# Main.net
KiCad netlist of a schematic drawn in Altium Designer
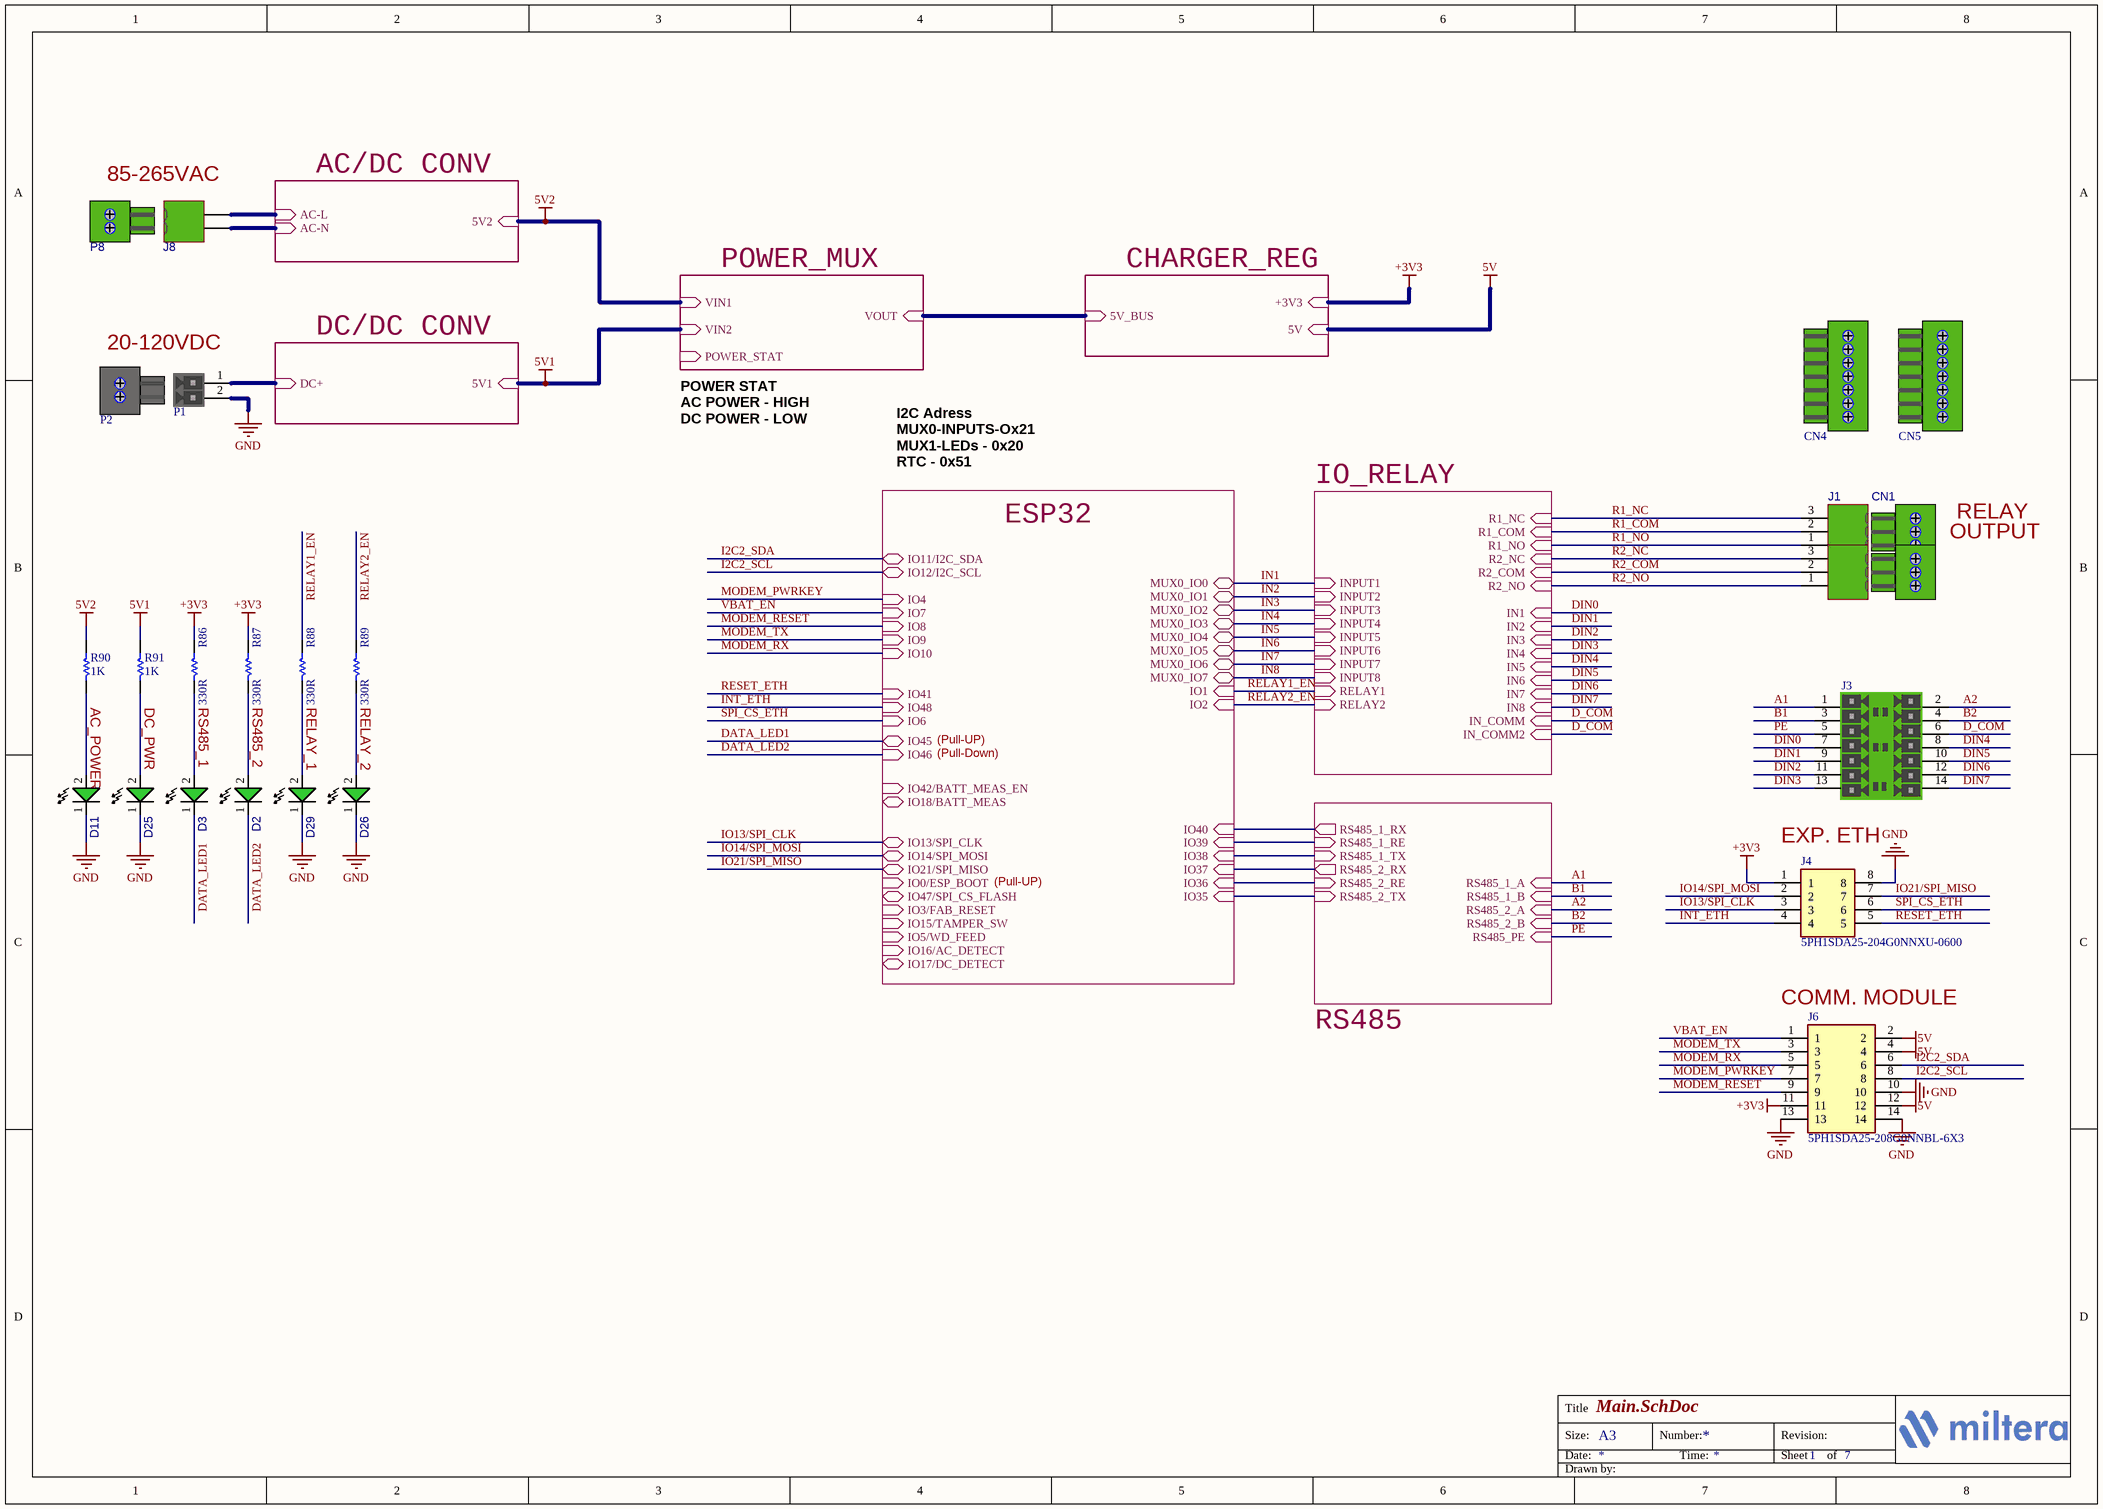
[diagram p0: Main.SchDoc]

(export (version "E")
  (design (tool "Eeschema 10.0.6"))
  (components
    (comp (ref "CN1")
      (value "2EDGK-5.08-06P-14-00AH")
      (footprint "2EDGK-5.08-06P-14-00AH")
      (description "TERM.BLK.5.08MM 6P FEMALE GREEN")
      (fields (field (name "MANUFACTURER") "DEGSON"))
      (libsource (lib "Connectors") (part "2EDGK-5.08-03P-14-00AH"))
    )
    (comp (ref "CN2")
      (value "2EDGRC-5.08-03P-14-00SH")
      (footprint "2EDGRC-5.08-03P-14-00SH")
      (description "TERM.BLK.5.08MM 3P 90C MALE GREEN CLOSED")
      (fields (field (name "MANUFACTURER") "GAOSONG"))
      (libsource (lib "Connectors") (part "2EDGRC-5.08-03P-14-00SH"))
    )
    (comp (ref "CN3")
      (value "2EDGK-5.08-03P-14-00AH")
      (footprint "2EDGK-5.08-06P-14-00AH")
      (description "TERM.BLK.5.08MM 3P FEMALE GREEN")
      (fields (field (name "MANUFACTURER") "DEGSON"))
      (libsource (lib "Connectors") (part "2EDGK-5.08-03P-14-00AH"))
    )
    (comp (ref "CN4")
      (value "15EDGK-3.81-07P-14-00AH")
      (footprint "15EDGK-3.81-07P")
      (description "TERM.BLK.3.81MM 7P FEMALE GREEN")
      (fields (field (name "MANUFACTURER") "DEGSON"))
      (libsource (lib "MTOSOS_R02") (part "15EDGK-3.81-07P-14-00AH"))
    )
    (comp (ref "CN5")
      (value "15EDGK-3.81-07P-14-00AH")
      (footprint "15EDGK-3.81-07P")
      (description "TERM.BLK.3.81MM 7P FEMALE GREEN")
      (fields (field (name "MANUFACTURER") "DEGSON"))
      (libsource (lib "MTOSOS_R02") (part "15EDGK-3.81-07P-14-00AH"))
    )
    (comp (ref "D2")
      (value "PSC-1608U52GC-G4")
      (footprint "LED_0603_GRN")
      (description "LED GREEN WATER CLEAR 0603 SMD")
      (fields (field (name "MANUFACTURER") "HONGLITRONIC"))
      (libsource (lib "Semiconductors") (part "LTST-C190TGKT"))
    )
    (comp (ref "D3")
      (value "PSC-1608U52GC-G4")
      (footprint "LED_0603_GRN")
      (description "LED GREEN WATER CLEAR 0603 SMD")
      (fields (field (name "MANUFACTURER") "HONGLITRONIC"))
      (libsource (lib "Semiconductors") (part "LTST-C190TGKT"))
    )
    (comp (ref "D11")
      (value "PSC-1608U52GC-G4")
      (footprint "LED_0603_GRN")
      (description "LED GREEN WATER CLEAR 0603 SMD")
      (fields (field (name "MANUFACTURER") "HONGLITRONIC"))
      (libsource (lib "Semiconductors") (part "LTST-C190TGKT"))
    )
    (comp (ref "D25")
      (value "PSC-1608U52GC-G4")
      (footprint "LED_0603_GRN")
      (description "LED GREEN WATER CLEAR 0603 SMD")
      (fields (field (name "MANUFACTURER") "HONGLITRONIC"))
      (libsource (lib "Semiconductors") (part "LTST-C190TGKT"))
    )
    (comp (ref "D26")
      (value "PSC-1608U52GC-G4")
      (footprint "LED_0603_GRN")
      (description "LED GREEN WATER CLEAR 0603 SMD")
      (fields (field (name "MANUFACTURER") "HONGLITRONIC"))
      (libsource (lib "Semiconductors") (part "LTST-C190TGKT"))
    )
    (comp (ref "D29")
      (value "PSC-1608U52GC-G4")
      (footprint "LED_0603_GRN")
      (description "LED GREEN WATER CLEAR 0603 SMD")
      (fields (field (name "MANUFACTURER") "HONGLITRONIC"))
      (libsource (lib "Semiconductors") (part "LTST-C190TGKT"))
    )
    (comp (ref "J1")
      (value "2EDGRC-5.08-06P-14-00SH")
      (footprint "2EDGRC-5.08-03P-14-00SH")
      (description "TERM.BLK.5.08MM 6P 90C MALE GREEN CLOSED")
      (fields (field (name "MANUFACTURER") "DEGSON"))
      (libsource (lib "Connectors") (part "2EDGRC-5.08-03P-14-00SH"))
    )
    (comp (ref "J3")
      (value "15EDGRH-3.81-12P-14-00AH")
      (footprint "15EDGRH-3.81-14P")
      (description "TERM.BLK.3.81mm 14P 90C MALE GREEN CLOSED")
      (fields (field (name "MANUFACTURER") "DEGSON"))
      (libsource (lib "MTOSOS_R02") (part "15EDGRH-3.81-12P-14-00AH"))
    )
    (comp (ref "J4")
      (value "5PH1SDA25-204G0NNXU-0600")
      (footprint "SamacSys:61300821121")
      (description "MALE HEADER 8PIN(2X4) 2.54MM THT 6X3MM")
      (fields (field (name "MANUFACTURER") "AMTEK"))
      (libsource (lib "*") (part "61300821121"))
    )
    (comp (ref "J6")
      (value "5PH1SDA25-208G0NNBL-6X3")
      (footprint "SamacSys:HDRV14W64P254_2X7_1778X508X854P")
      (description "PIN HEADER 16PIN(2x8) 2.54mm THT V/T")
      (fields (field (name "MANUFACTURER") "AMTEK"))
      (libsource (lib "*") (part "61301421121"))
    )
    (comp (ref "J8")
      (value "2EDGRC-5.08-02P-14-00AH")
      (footprint "2EDGRC-5.08-02P")
      (description "TERM.BLK.5.08MM 2P 90C MALE GREEN CLOSED")
      (fields (field (name "MANUFACTURER") "DEGSON"))
      (libsource (lib "MTOSOS_R02") (part "2EDGRC-5.08-02P-14-00AH"))
    )
    (comp (ref "P1")
      (value "15EDGRC-3.5-02P-11-00AH")
      (footprint "15EDGRC-3.5-02P-11-00AH")
      (description "TERM.BLK.3.50MM 2P 90C MALE GRAY CLOSED")
      (fields (field (name "MANUFACTURER") "DEGSON"))
      (libsource (lib "MTOSOS_R02") (part "15EDGRC-3.5-02P-11-00AH"))
    )
    (comp (ref "P2")
      (value "15EDGK-3.5-02P-11-00AH")
      (footprint "15EDGK-3.5-02P-11-00AH")
      (description "TERM.BLK.3.50MM 2P FEMALE GRAY")
      (fields (field (name "MANUFACTURER") "DEGSON"))
      (libsource (lib "MTOSOS_R02") (part "15EDGK-3.5-02P-11-00AH"))
    )
    (comp (ref "P8")
      (value "2EDGK-5.08-02P-14-00AH")
      (footprint "2EDGK-5.08-02P")
      (description "TERM.BLK.5.08MM 2P FEMALE GREEN")
      (fields (field (name "MANUFACTURER") "DEGSON"))
      (libsource (lib "MTOSOS_R02") (part "2EDGK-5.08-02P-14-00AH"))
    )
    (comp (ref "R86")
      (value "330R")
      (footprint "RES_0603")
      (description "RES 0603 330 Ohms 1% 1/10W-S 100PPM")
      (fields
        (field (name "MANUFACTURER") "ROYALOHM")
        (field (name "MANUFACTURER PART NUMBER") "0603SAF3300T5E")
      )
      (libsource (lib "open-components") (part "RES"))
    )
    (comp (ref "R87")
      (value "330R")
      (footprint "RES_0603")
      (description "RES 0603 330 Ohms 1% 1/10W-S 100PPM")
      (fields
        (field (name "MANUFACTURER") "ROYALOHM")
        (field (name "MANUFACTURER PART NUMBER") "0603SAF3300T5E")
      )
      (libsource (lib "open-components") (part "RES"))
    )
    (comp (ref "R88")
      (value "330R")
      (footprint "RES_0603")
      (description "RES 0603 330 Ohms 1% 1/10W-S 100PPM")
      (fields
        (field (name "MANUFACTURER") "ROYALOHM")
        (field (name "MANUFACTURER PART NUMBER") "0603SAF3300T5E")
      )
      (libsource (lib "open-components") (part "RES"))
    )
    (comp (ref "R89")
      (value "330R")
      (footprint "RES_0603")
      (description "RES 0603 330 Ohms 1% 1/10W-S 100PPM")
      (fields
        (field (name "MANUFACTURER") "ROYALOHM")
        (field (name "MANUFACTURER PART NUMBER") "0603SAF3300T5E")
      )
      (libsource (lib "open-components") (part "RES"))
    )
    (comp (ref "R90")
      (value "1K")
      (footprint "RES_0603")
      (description "RES 0603 1K Ohms 1% 1/10W-S 100PPM")
      (fields
        (field (name "MANUFACTURER") "ROYALOHM")
        (field (name "MANUFACTURER PART NUMBER") "0603SAF1001T5E")
      )
      (libsource (lib "open-components") (part "RES"))
    )
    (comp (ref "R91")
      (value "1K")
      (footprint "RES_0603")
      (description "RES 0603 1K Ohms 1% 1/10W-S 100PPM")
      (fields
        (field (name "MANUFACTURER") "ROYALOHM")
        (field (name "MANUFACTURER PART NUMBER") "0603SAF1001T5E")
      )
      (libsource (lib "open-components") (part "RES"))
    )
  )
  (nets
    (net (code "1") (name "+3V3") (class "Default")
      (node (ref "J4") (pin "1") (pinfunction "1_1") (pintype "passive"))
      (node (ref "J6") (pin "11") (pinfunction "11_11") (pintype "passive"))
      (node (ref "R86") (pin "1") (pinfunction "1_1") (pintype "passive"))
      (node (ref "R87") (pin "1") (pinfunction "1_1") (pintype "passive"))
    )
    (net (code "3") (name "/A1") (class "Default")
      (node (ref "J3") (pin "1") (pinfunction "1_1") (pintype "passive"))
    )
    (net (code "4") (name "/A2") (class "Default")
      (node (ref "J3") (pin "2") (pinfunction "2_2") (pintype "passive"))
    )
    (net (code "5") (name "/AC-L") (class "Default")
      (node (ref "J8") (pin "1") (pinfunction "1_1") (pintype "passive"))
    )
    (net (code "6") (name "/AC-N") (class "Default")
      (node (ref "J8") (pin "2") (pinfunction "2_2") (pintype "passive"))
    )
    (net (code "7") (name "/B1") (class "Default")
      (node (ref "J3") (pin "3") (pinfunction "3_3") (pintype "passive"))
    )
    (net (code "8") (name "/B2") (class "Default")
      (node (ref "J3") (pin "4") (pinfunction "4_4") (pintype "passive"))
    )
    (net (code "9") (name "/DATA_LED1") (class "Default")
      (node (ref "D3") (pin "1") (pinfunction "1_1") (pintype "passive"))
    )
    (net (code "10") (name "/DATA_LED2") (class "Default")
      (node (ref "D2") (pin "1") (pinfunction "1_1") (pintype "passive"))
    )
    (net (code "11") (name "/DC+") (class "Default")
      (node (ref "P1") (pin "1") (pinfunction "1_1") (pintype "passive"))
    )
    (net (code "12") (name "/DIN0") (class "Default")
      (node (ref "J3") (pin "7") (pinfunction "7_7") (pintype "passive"))
    )
    (net (code "13") (name "/DIN1") (class "Default")
      (node (ref "J3") (pin "9") (pinfunction "9_9") (pintype "passive"))
    )
    (net (code "14") (name "/DIN2") (class "Default")
      (node (ref "J3") (pin "11") (pinfunction "11_11") (pintype "passive"))
    )
    (net (code "15") (name "/DIN3") (class "Default")
      (node (ref "J3") (pin "13") (pinfunction "13_13") (pintype "passive"))
    )
    (net (code "16") (name "/DIN4") (class "Default")
      (node (ref "J3") (pin "8") (pinfunction "8_8") (pintype "passive"))
    )
    (net (code "17") (name "/DIN5") (class "Default")
      (node (ref "J3") (pin "10") (pinfunction "10_10") (pintype "passive"))
    )
    (net (code "18") (name "/DIN6") (class "Default")
      (node (ref "J3") (pin "12") (pinfunction "12_12") (pintype "passive"))
    )
    (net (code "19") (name "/DIN7") (class "Default")
      (node (ref "J3") (pin "14") (pinfunction "14_14") (pintype "passive"))
    )
    (net (code "20") (name "/D_COM") (class "Default")
      (node (ref "J3") (pin "6") (pinfunction "6_6") (pintype "passive"))
    )
    (net (code "21") (name "/I2C2_SCL") (class "Default")
      (node (ref "J6") (pin "8") (pinfunction "8_8") (pintype "passive"))
    )
    (net (code "22") (name "/I2C2_SDA") (class "Default")
      (node (ref "J6") (pin "6") (pinfunction "6_6") (pintype "passive"))
    )
    (net (code "31") (name "/INT_ETH") (class "Default")
      (node (ref "J4") (pin "4") (pinfunction "4_4") (pintype "passive"))
    )
    (net (code "35") (name "/IO13{slash}SPI_CLK") (class "Default")
      (node (ref "J4") (pin "3") (pinfunction "3_3") (pintype "passive"))
    )
    (net (code "36") (name "/IO14{slash}SPI_MOSI") (class "Default")
      (node (ref "J4") (pin "2") (pinfunction "2_2") (pintype "passive"))
    )
    (net (code "41") (name "/IO21{slash}SPI_MISO") (class "Default")
      (node (ref "J4") (pin "7") (pinfunction "7_7") (pintype "passive"))
    )
    (net (code "48") (name "/MODEM_PWRKEY") (class "Default")
      (node (ref "J6") (pin "7") (pinfunction "7_7") (pintype "passive"))
    )
    (net (code "49") (name "/MODEM_RESET") (class "Default")
      (node (ref "J6") (pin "9") (pinfunction "9_9") (pintype "passive"))
    )
    (net (code "50") (name "/MODEM_RX") (class "Default")
      (node (ref "J6") (pin "5") (pinfunction "5_5") (pintype "passive"))
    )
    (net (code "51") (name "/MODEM_TX") (class "Default")
      (node (ref "J6") (pin "3") (pinfunction "3_3") (pintype "passive"))
    )
    (net (code "52") (name "/PE") (class "Default")
      (node (ref "J3") (pin "5") (pinfunction "5_5") (pintype "passive"))
    )
    (net (code "54") (name "/R1_COM") (class "Default")
      (node (ref "J1") (pin "2") (pinfunction "2_2") (pintype "passive"))
    )
    (net (code "55") (name "/R1_NC") (class "Default")
      (node (ref "J1") (pin "3") (pinfunction "3_3") (pintype "passive"))
    )
    (net (code "56") (name "/R1_NO") (class "Default")
      (node (ref "J1") (pin "1") (pinfunction "1_1") (pintype "passive"))
    )
    (net (code "57") (name "/R2_COM") (class "Default")
      (node (ref "CN2") (pin "2") (pinfunction "2_2") (pintype "passive"))
    )
    (net (code "58") (name "/R2_NC") (class "Default")
      (node (ref "CN2") (pin "3") (pinfunction "3_3") (pintype "passive"))
    )
    (net (code "59") (name "/R2_NO") (class "Default")
      (node (ref "CN2") (pin "1") (pinfunction "1_1") (pintype "passive"))
    )
    (net (code "60") (name "/RELAY1_EN") (class "Default")
      (node (ref "R88") (pin "1") (pinfunction "1_1") (pintype "passive"))
    )
    (net (code "61") (name "/RELAY2_EN") (class "Default")
      (node (ref "R89") (pin "1") (pinfunction "1_1") (pintype "passive"))
    )
    (net (code "62") (name "/RESET_ETH") (class "Default")
      (node (ref "J4") (pin "5") (pinfunction "5_5") (pintype "passive"))
    )
    (net (code "65") (name "/SPI_CS_ETH") (class "Default")
      (node (ref "J4") (pin "6") (pinfunction "6_6") (pintype "passive"))
    )
    (net (code "66") (name "/VBAT_EN") (class "Default")
      (node (ref "J6") (pin "1") (pinfunction "1_1") (pintype "passive"))
    )
    (net (code "67") (name "5V") (class "Default")
      (node (ref "J6") (pin "12") (pinfunction "12_12") (pintype "passive"))
      (node (ref "J6") (pin "2") (pinfunction "2_2") (pintype "passive"))
      (node (ref "J6") (pin "4") (pinfunction "4_4") (pintype "passive"))
    )
    (net (code "68") (name "5V1") (class "Default")
      (node (ref "R91") (pin "1") (pinfunction "1_1") (pintype "passive"))
    )
    (net (code "69") (name "5V2") (class "Default")
      (node (ref "R90") (pin "1") (pinfunction "1_1") (pintype "passive"))
    )
    (net (code "70") (name "GND") (class "Default")
      (node (ref "D11") (pin "1") (pinfunction "1_1") (pintype "passive"))
      (node (ref "D25") (pin "1") (pinfunction "1_1") (pintype "passive"))
      (node (ref "D26") (pin "1") (pinfunction "1_1") (pintype "passive"))
      (node (ref "D29") (pin "1") (pinfunction "1_1") (pintype "passive"))
      (node (ref "J4") (pin "8") (pinfunction "8_8") (pintype "passive"))
      (node (ref "J6") (pin "10") (pinfunction "10_10") (pintype "passive"))
      (node (ref "J6") (pin "13") (pinfunction "13_13") (pintype "passive"))
      (node (ref "J6") (pin "14") (pinfunction "14_14") (pintype "passive"))
      (node (ref "P1") (pin "2") (pinfunction "2_2") (pintype "passive"))
    )
    (net (code "71") (name "Net-(D2-Pad2)") (class "Default")
      (node (ref "D2") (pin "2") (pinfunction "2_2") (pintype "passive"))
      (node (ref "R87") (pin "2") (pinfunction "2_2") (pintype "passive"))
    )
    (net (code "72") (name "Net-(D3-Pad2)") (class "Default")
      (node (ref "D3") (pin "2") (pinfunction "2_2") (pintype "passive"))
      (node (ref "R86") (pin "2") (pinfunction "2_2") (pintype "passive"))
    )
    (net (code "73") (name "Net-(D11-Pad2)") (class "Default")
      (node (ref "D11") (pin "2") (pinfunction "2_2") (pintype "passive"))
      (node (ref "R90") (pin "2") (pinfunction "2_2") (pintype "passive"))
    )
    (net (code "74") (name "Net-(D25-Pad2)") (class "Default")
      (node (ref "D25") (pin "2") (pinfunction "2_2") (pintype "passive"))
      (node (ref "R91") (pin "2") (pinfunction "2_2") (pintype "passive"))
    )
    (net (code "75") (name "Net-(D26-Pad2)") (class "Default")
      (node (ref "D26") (pin "2") (pinfunction "2_2") (pintype "passive"))
      (node (ref "R89") (pin "2") (pinfunction "2_2") (pintype "passive"))
    )
    (net (code "76") (name "Net-(D29-Pad2)") (class "Default")
      (node (ref "D29") (pin "2") (pinfunction "2_2") (pintype "passive"))
      (node (ref "R88") (pin "2") (pinfunction "2_2") (pintype "passive"))
    )
  )
)
